# QUTMS-BrakeLight-S01.net
KiCad netlist of a schematic drawn in Altium Designer
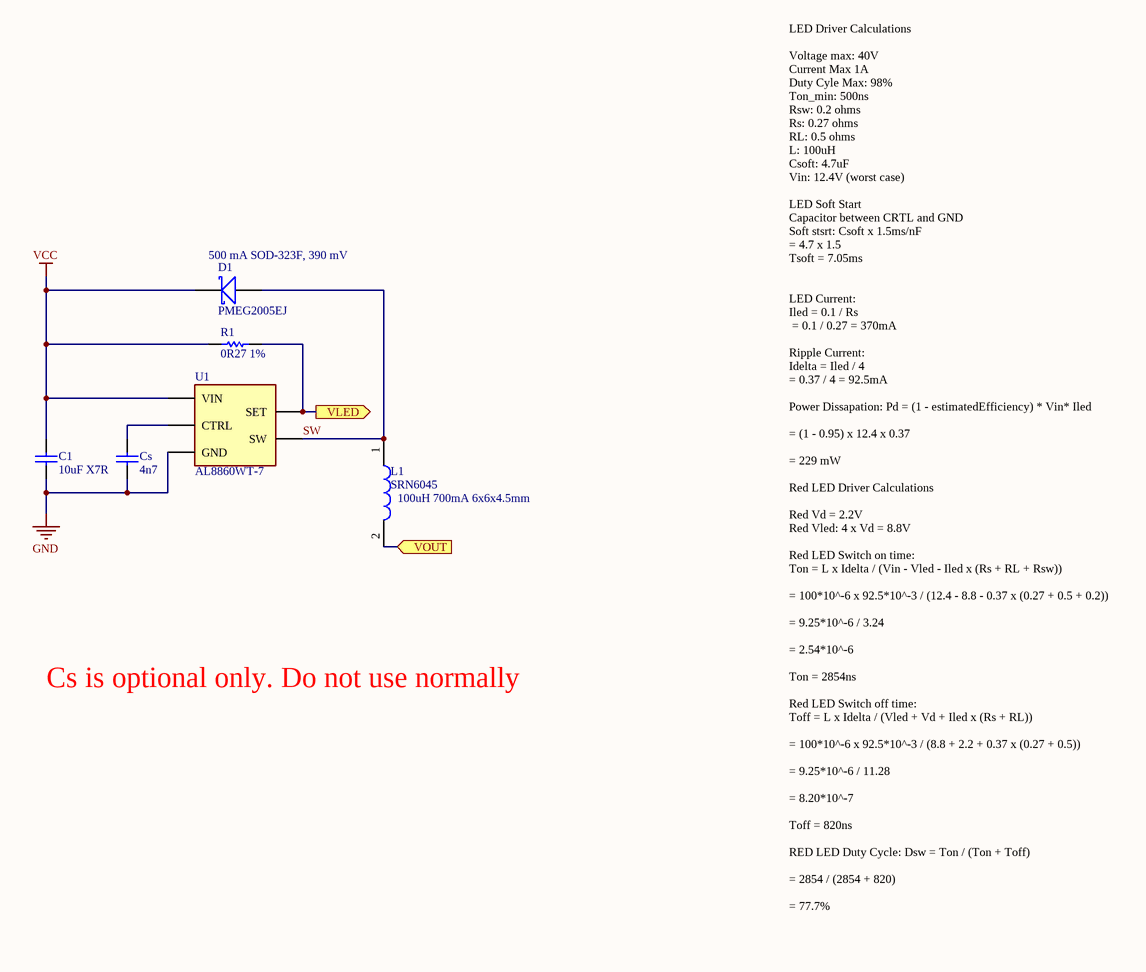
[diagram p0: QUTMS-BrakeLight-S01.SchDoc]

(export (version "E")
  (design (tool "Eeschema 10.0.6"))
  (components
    (comp (ref "C1")
      (value "10uF X7R")
      (footprint "Cap_Ceramic_0603")
      (description "Capacitor, Ceramic, SMD, 10uF, 50V, 5%, X7R, 0603")
      (libsource (lib "StandardCapacitors") (part "10uF 50V 5% X7R 0603"))
    )
    (comp (ref "Cs")
      (value "4n7")
      (footprint "Cap_Ceramic_0603")
      (description "Capacitor, Ceramic, SMD, 4n7, 25V, 5%, X7R, 0603")
      (libsource (lib "StandardCapacitors") (part "4n7 25V 5% X7R 0603"))
    )
    (comp (ref "D1")
      (value "PMEG2005EJ")
      (footprint "SOD-323F")
      (description "PMEG2005EJ,115 -  Schottky Rectifier, 20 V, 500 mA, Single, SOD-323F, 2 Pins, 390 mV")
      (libsource (lib "QUTMS_DiodeLibrary") (part "PMEG2005EJ"))
    )
    (comp (ref "L1")
      (value "SRN6045")
      (footprint "Bourns Inductor 6x6x4.5mm")
      (description "Power Inductor (SMD), 100 µH, 700 mA, Semishielded, 800 mA")
      (libsource (lib "QUTMS_InductorLibrary") (part "SRN6045"))
    )
    (comp (ref "R1")
      (value "0R27 1%")
      (footprint "Res_ThinFilm_0603")
      (libsource (lib "StandardResistors") (part "0R27 1% 0603"))
    )
    (comp (ref "U1")
      (value "AL8860WT-7")
      (footprint "TSOT-25")
      (libsource (lib "QUTMS_PowerSupplyLibrary") (part "AL8860WT-7"))
    )
  )
  (nets
    (net (code "1") (name "/SW") (class "Default")
      (node (ref "D1") (pin "A") (pinfunction "Anode_A") (pintype "passive"))
      (node (ref "L1") (pin "1") (pinfunction "1_1") (pintype "passive"))
      (node (ref "U1") (pin "1") (pinfunction "SW_1") (pintype "power_in"))
    )
    (net (code "2") (name "/VLED") (class "Default")
      (node (ref "R1") (pin "2") (pinfunction "2_2") (pintype "passive"))
      (node (ref "U1") (pin "4") (pinfunction "SET_4") (pintype "power_in"))
    )
    (net (code "3") (name "/VOUT") (class "Default")
      (node (ref "L1") (pin "2") (pinfunction "2_2") (pintype "passive"))
    )
    (net (code "4") (name "GND") (class "Default")
      (node (ref "C1") (pin "1") (pinfunction "1_1") (pintype "passive"))
      (node (ref "Cs") (pin "1") (pinfunction "1_1") (pintype "passive"))
      (node (ref "U1") (pin "2") (pinfunction "GND_2") (pintype "power_in"))
    )
    (net (code "5") (name "Net-(U1-CTRL)") (class "Default")
      (node (ref "Cs") (pin "2") (pinfunction "2_2") (pintype "passive"))
      (node (ref "U1") (pin "3") (pinfunction "CTRL_3") (pintype "power_in"))
    )
    (net (code "6") (name "VCC") (class "Default")
      (node (ref "C1") (pin "2") (pinfunction "2_2") (pintype "passive"))
      (node (ref "D1") (pin "K") (pinfunction "Cathode_K") (pintype "passive"))
      (node (ref "R1") (pin "1") (pinfunction "1_1") (pintype "passive"))
      (node (ref "U1") (pin "5") (pinfunction "VIN_5") (pintype "power_in"))
    )
  )
)
